# 05_-_NIXIE.net
KiCad netlist of a schematic drawn in Altium Designer
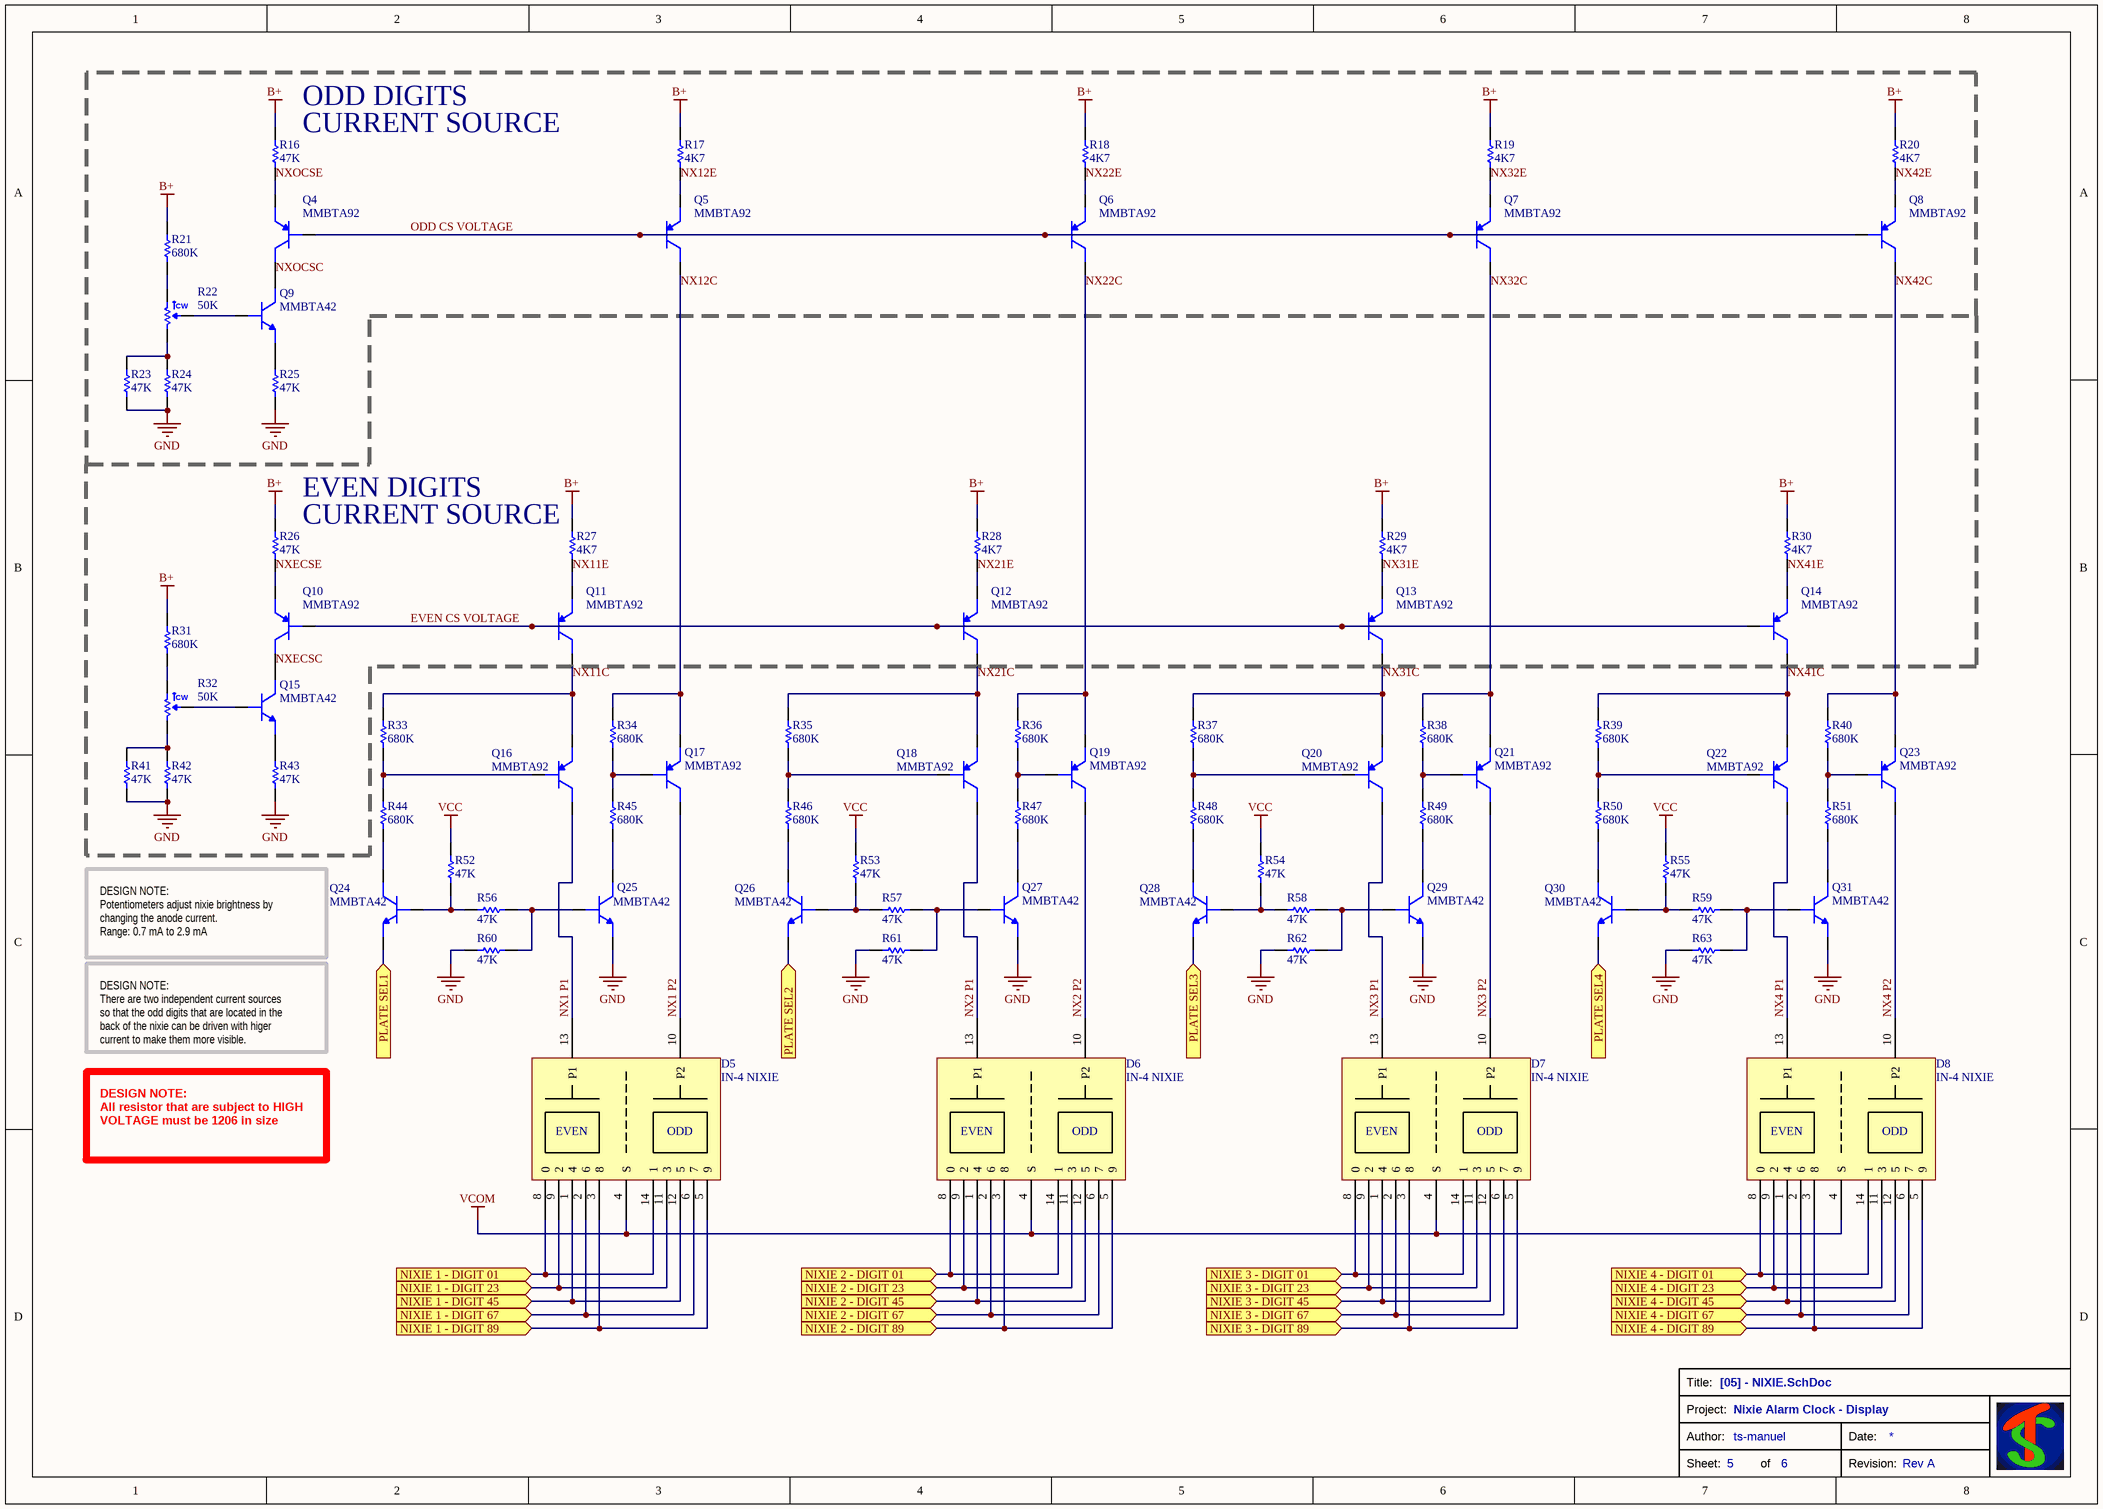
[diagram p0: [05] - NIXIE.SchDoc]

(export (version "E")
  (design (tool "Eeschema 10.0.6"))
  (components
    (comp (ref "D5")
      (value "IN-4 NIXIE")
      (footprint "IN4 NIXIE")
      (libsource (lib "mt_local_library") (part "IN-4 NIXIE"))
    )
    (comp (ref "D6")
      (value "IN-4 NIXIE")
      (footprint "IN4 NIXIE")
      (libsource (lib "mt_local_library") (part "IN-4 NIXIE"))
    )
    (comp (ref "D7")
      (value "IN-4 NIXIE")
      (footprint "IN4 NIXIE")
      (libsource (lib "mt_local_library") (part "IN-4 NIXIE"))
    )
    (comp (ref "D8")
      (value "IN-4 NIXIE")
      (footprint "IN4 NIXIE")
      (libsource (lib "mt_local_library") (part "IN-4 NIXIE"))
    )
    (comp (ref "Q4")
      (value "MMBTA92")
      (footprint "SOT95P240X110-3N")
      (description "300V PNP SMALL SIGNAL TRANSISTOR IN SOT23")
      (libsource (lib "mt_local_library") (part "PNP-MMBTA92"))
    )
    (comp (ref "Q5")
      (value "MMBTA92")
      (footprint "SOT95P240X110-3N")
      (description "300V PNP SMALL SIGNAL TRANSISTOR IN SOT23")
      (libsource (lib "mt_local_library") (part "PNP-MMBTA92"))
    )
    (comp (ref "Q6")
      (value "MMBTA92")
      (footprint "SOT95P240X110-3N")
      (description "300V PNP SMALL SIGNAL TRANSISTOR IN SOT23")
      (libsource (lib "mt_local_library") (part "PNP-MMBTA92"))
    )
    (comp (ref "Q7")
      (value "MMBTA92")
      (footprint "SOT95P240X110-3N")
      (description "300V PNP SMALL SIGNAL TRANSISTOR IN SOT23")
      (libsource (lib "mt_local_library") (part "PNP-MMBTA92"))
    )
    (comp (ref "Q8")
      (value "MMBTA92")
      (footprint "SOT95P240X110-3N")
      (description "300V PNP SMALL SIGNAL TRANSISTOR IN SOT23")
      (libsource (lib "mt_local_library") (part "PNP-MMBTA92"))
    )
    (comp (ref "Q9")
      (value "MMBTA42")
      (footprint "SOT95P240X110-3N")
      (description "300V NPN SMALL SIGNAL TRANSISTOR IN SOT23")
      (libsource (lib "mt_local_library") (part "NPN-MMBTA42"))
    )
    (comp (ref "Q10")
      (value "MMBTA92")
      (footprint "SOT95P240X110-3N")
      (description "300V PNP SMALL SIGNAL TRANSISTOR IN SOT23")
      (libsource (lib "mt_local_library") (part "PNP-MMBTA92"))
    )
    (comp (ref "Q11")
      (value "MMBTA92")
      (footprint "SOT95P240X110-3N")
      (description "300V PNP SMALL SIGNAL TRANSISTOR IN SOT23")
      (libsource (lib "mt_local_library") (part "PNP-MMBTA92"))
    )
    (comp (ref "Q12")
      (value "MMBTA92")
      (footprint "SOT95P240X110-3N")
      (description "300V PNP SMALL SIGNAL TRANSISTOR IN SOT23")
      (libsource (lib "mt_local_library") (part "PNP-MMBTA92"))
    )
    (comp (ref "Q13")
      (value "MMBTA92")
      (footprint "SOT95P240X110-3N")
      (description "300V PNP SMALL SIGNAL TRANSISTOR IN SOT23")
      (libsource (lib "mt_local_library") (part "PNP-MMBTA92"))
    )
    (comp (ref "Q14")
      (value "MMBTA92")
      (footprint "SOT95P240X110-3N")
      (description "300V PNP SMALL SIGNAL TRANSISTOR IN SOT23")
      (libsource (lib "mt_local_library") (part "PNP-MMBTA92"))
    )
    (comp (ref "Q15")
      (value "MMBTA42")
      (footprint "SOT95P240X110-3N")
      (description "300V NPN SMALL SIGNAL TRANSISTOR IN SOT23")
      (libsource (lib "mt_local_library") (part "NPN-MMBTA42"))
    )
    (comp (ref "Q16")
      (value "MMBTA92")
      (footprint "SOT95P240X110-3N")
      (description "300V PNP SMALL SIGNAL TRANSISTOR IN SOT23")
      (libsource (lib "mt_local_library") (part "PNP-MMBTA92"))
    )
    (comp (ref "Q17")
      (value "MMBTA92")
      (footprint "SOT95P240X110-3N")
      (description "300V PNP SMALL SIGNAL TRANSISTOR IN SOT23")
      (libsource (lib "mt_local_library") (part "PNP-MMBTA92"))
    )
    (comp (ref "Q18")
      (value "MMBTA92")
      (footprint "SOT95P240X110-3N")
      (description "300V PNP SMALL SIGNAL TRANSISTOR IN SOT23")
      (libsource (lib "mt_local_library") (part "PNP-MMBTA92"))
    )
    (comp (ref "Q19")
      (value "MMBTA92")
      (footprint "SOT95P240X110-3N")
      (description "300V PNP SMALL SIGNAL TRANSISTOR IN SOT23")
      (libsource (lib "mt_local_library") (part "PNP-MMBTA92"))
    )
    (comp (ref "Q20")
      (value "MMBTA92")
      (footprint "SOT95P240X110-3N")
      (description "300V PNP SMALL SIGNAL TRANSISTOR IN SOT23")
      (libsource (lib "mt_local_library") (part "PNP-MMBTA92"))
    )
    (comp (ref "Q21")
      (value "MMBTA92")
      (footprint "SOT95P240X110-3N")
      (description "300V PNP SMALL SIGNAL TRANSISTOR IN SOT23")
      (libsource (lib "mt_local_library") (part "PNP-MMBTA92"))
    )
    (comp (ref "Q22")
      (value "MMBTA92")
      (footprint "SOT95P240X110-3N")
      (description "300V PNP SMALL SIGNAL TRANSISTOR IN SOT23")
      (libsource (lib "mt_local_library") (part "PNP-MMBTA92"))
    )
    (comp (ref "Q23")
      (value "MMBTA92")
      (footprint "SOT95P240X110-3N")
      (description "300V PNP SMALL SIGNAL TRANSISTOR IN SOT23")
      (libsource (lib "mt_local_library") (part "PNP-MMBTA92"))
    )
    (comp (ref "Q24")
      (value "MMBTA42")
      (footprint "SOT95P240X110-3N")
      (description "300V NPN SMALL SIGNAL TRANSISTOR IN SOT23")
      (libsource (lib "mt_local_library") (part "NPN-MMBTA42"))
    )
    (comp (ref "Q25")
      (value "MMBTA42")
      (footprint "SOT95P240X110-3N")
      (description "300V NPN SMALL SIGNAL TRANSISTOR IN SOT23")
      (libsource (lib "mt_local_library") (part "NPN-MMBTA42"))
    )
    (comp (ref "Q26")
      (value "MMBTA42")
      (footprint "SOT95P240X110-3N")
      (description "300V NPN SMALL SIGNAL TRANSISTOR IN SOT23")
      (libsource (lib "mt_local_library") (part "NPN-MMBTA42"))
    )
    (comp (ref "Q27")
      (value "MMBTA42")
      (footprint "SOT95P240X110-3N")
      (description "300V NPN SMALL SIGNAL TRANSISTOR IN SOT23")
      (libsource (lib "mt_local_library") (part "NPN-MMBTA42"))
    )
    (comp (ref "Q28")
      (value "MMBTA42")
      (footprint "SOT95P240X110-3N")
      (description "300V NPN SMALL SIGNAL TRANSISTOR IN SOT23")
      (libsource (lib "mt_local_library") (part "NPN-MMBTA42"))
    )
    (comp (ref "Q29")
      (value "MMBTA42")
      (footprint "SOT95P240X110-3N")
      (description "300V NPN SMALL SIGNAL TRANSISTOR IN SOT23")
      (libsource (lib "mt_local_library") (part "NPN-MMBTA42"))
    )
    (comp (ref "Q30")
      (value "MMBTA42")
      (footprint "SOT95P240X110-3N")
      (description "300V NPN SMALL SIGNAL TRANSISTOR IN SOT23")
      (libsource (lib "mt_local_library") (part "NPN-MMBTA42"))
    )
    (comp (ref "Q31")
      (value "MMBTA42")
      (footprint "SOT95P240X110-3N")
      (description "300V NPN SMALL SIGNAL TRANSISTOR IN SOT23")
      (libsource (lib "mt_local_library") (part "NPN-MMBTA42"))
    )
    (comp (ref "R16")
      (value "47K")
      (footprint "RES-0805")
      (description "Thin Film Resistors 1/8W 47K ohm 1% 50ppm")
      (fields (field (name "MANUFACTURER") "Yageo") (field (name "TOLERANCE") "1%"))
      (libsource (lib "mt_local_library") (part "RES-0805-47K-RT0805FRE0747KL"))
    )
    (comp (ref "R17")
      (value "4K7")
      (footprint "RES-0805")
      (description "Thin Film Resistors 4.7K ohm 1% 50 ppm")
      (fields (field (name "MANUFACTURER") "Yageo") (field (name "TOLERANCE") "1%"))
      (libsource (lib "mt_local_library") (part "RES-0805-4K7-RT0805FRE134K7L"))
    )
    (comp (ref "R18")
      (value "4K7")
      (footprint "RES-0805")
      (description "Thin Film Resistors 4.7K ohm 1% 50 ppm")
      (fields (field (name "MANUFACTURER") "Yageo") (field (name "TOLERANCE") "1%"))
      (libsource (lib "mt_local_library") (part "RES-0805-4K7-RT0805FRE134K7L"))
    )
    (comp (ref "R19")
      (value "4K7")
      (footprint "RES-0805")
      (description "Thin Film Resistors 4.7K ohm 1% 50 ppm")
      (fields (field (name "MANUFACTURER") "Yageo") (field (name "TOLERANCE") "1%"))
      (libsource (lib "mt_local_library") (part "RES-0805-4K7-RT0805FRE134K7L"))
    )
    (comp (ref "R20")
      (value "4K7")
      (footprint "RES-0805")
      (description "Thin Film Resistors 4.7K ohm 1% 50 ppm")
      (fields (field (name "MANUFACTURER") "Yageo") (field (name "TOLERANCE") "1%"))
      (libsource (lib "mt_local_library") (part "RES-0805-4K7-RT0805FRE134K7L"))
    )
    (comp (ref "R21")
      (value "680K")
      (footprint "RES-1206")
      (description "Thin Film Resistors 680K OHM 1% 50PPM 1/4W")
      (fields (field (name "MANUFACTURER") "Yageo") (field (name "TOLERANCE") "1%"))
      (libsource (lib "mt_local_library") (part "RES-1206-680K-RT1206FRE07680KL"))
    )
    (comp (ref "R22")
      (value "50K")
      (footprint "TC33X2503E")
      (description "Resistenze trimmer - SMD 3MM 50KOHMS 25% 0.1WATT OPEN FRM")
      (fields (field (name "MANUFACTURER") "Yageo") (field (name "TOLERANCE") "1%"))
      (libsource (lib "mt_local_library") (part "POT-50K-TC33X-2-503E"))
    )
    (comp (ref "R23")
      (value "47K")
      (footprint "RES-0805")
      (description "Thin Film Resistors 1/8W 47K ohm 1% 50ppm")
      (fields (field (name "MANUFACTURER") "Yageo") (field (name "TOLERANCE") "1%"))
      (libsource (lib "mt_local_library") (part "RES-0805-47K-RT0805FRE0747KL"))
    )
    (comp (ref "R24")
      (value "47K")
      (footprint "RES-0805")
      (description "Thin Film Resistors 1/8W 47K ohm 1% 50ppm")
      (fields (field (name "MANUFACTURER") "Yageo") (field (name "TOLERANCE") "1%"))
      (libsource (lib "mt_local_library") (part "RES-0805-47K-RT0805FRE0747KL"))
    )
    (comp (ref "R25")
      (value "47K")
      (footprint "RES-0805")
      (description "Thin Film Resistors 1/8W 47K ohm 1% 50ppm")
      (fields (field (name "MANUFACTURER") "Yageo") (field (name "TOLERANCE") "1%"))
      (libsource (lib "mt_local_library") (part "RES-0805-47K-RT0805FRE0747KL"))
    )
    (comp (ref "R26")
      (value "47K")
      (footprint "RES-0805")
      (description "Thin Film Resistors 1/8W 47K ohm 1% 50ppm")
      (fields (field (name "MANUFACTURER") "Yageo") (field (name "TOLERANCE") "1%"))
      (libsource (lib "mt_local_library") (part "RES-0805-47K-RT0805FRE0747KL"))
    )
    (comp (ref "R27")
      (value "4K7")
      (footprint "RES-0805")
      (description "Thin Film Resistors 4.7K ohm 1% 50 ppm")
      (fields (field (name "MANUFACTURER") "Yageo") (field (name "TOLERANCE") "1%"))
      (libsource (lib "mt_local_library") (part "RES-0805-4K7-RT0805FRE134K7L"))
    )
    (comp (ref "R28")
      (value "4K7")
      (footprint "RES-0805")
      (description "Thin Film Resistors 4.7K ohm 1% 50 ppm")
      (fields (field (name "MANUFACTURER") "Yageo") (field (name "TOLERANCE") "1%"))
      (libsource (lib "mt_local_library") (part "RES-0805-4K7-RT0805FRE134K7L"))
    )
    (comp (ref "R29")
      (value "4K7")
      (footprint "RES-0805")
      (description "Thin Film Resistors 4.7K ohm 1% 50 ppm")
      (fields (field (name "MANUFACTURER") "Yageo") (field (name "TOLERANCE") "1%"))
      (libsource (lib "mt_local_library") (part "RES-0805-4K7-RT0805FRE134K7L"))
    )
    (comp (ref "R30")
      (value "4K7")
      (footprint "RES-0805")
      (description "Thin Film Resistors 4.7K ohm 1% 50 ppm")
      (fields (field (name "MANUFACTURER") "Yageo") (field (name "TOLERANCE") "1%"))
      (libsource (lib "mt_local_library") (part "RES-0805-4K7-RT0805FRE134K7L"))
    )
    (comp (ref "R31")
      (value "680K")
      (footprint "RES-1206")
      (description "Thin Film Resistors 680K OHM 1% 50PPM 1/4W")
      (fields (field (name "MANUFACTURER") "Yageo") (field (name "TOLERANCE") "1%"))
      (libsource (lib "mt_local_library") (part "RES-1206-680K-RT1206FRE07680KL"))
    )
    (comp (ref "R32")
      (value "50K")
      (footprint "TC33X2503E")
      (description "Resistenze trimmer - SMD 3MM 50KOHMS 25% 0.1WATT OPEN FRM")
      (fields (field (name "MANUFACTURER") "Yageo") (field (name "TOLERANCE") "1%"))
      (libsource (lib "mt_local_library") (part "POT-50K-TC33X-2-503E"))
    )
    (comp (ref "R33")
      (value "680K")
      (footprint "RES-1206")
      (description "Thin Film Resistors 680K OHM 1% 50PPM 1/4W")
      (fields (field (name "MANUFACTURER") "Yageo") (field (name "TOLERANCE") "1%"))
      (libsource (lib "mt_local_library") (part "RES-1206-680K-RT1206FRE07680KL"))
    )
    (comp (ref "R34")
      (value "680K")
      (footprint "RES-1206")
      (description "Thin Film Resistors 680K OHM 1% 50PPM 1/4W")
      (fields (field (name "MANUFACTURER") "Yageo") (field (name "TOLERANCE") "1%"))
      (libsource (lib "mt_local_library") (part "RES-1206-680K-RT1206FRE07680KL"))
    )
    (comp (ref "R35")
      (value "680K")
      (footprint "RES-1206")
      (description "Thin Film Resistors 680K OHM 1% 50PPM 1/4W")
      (fields (field (name "MANUFACTURER") "Yageo") (field (name "TOLERANCE") "1%"))
      (libsource (lib "mt_local_library") (part "RES-1206-680K-RT1206FRE07680KL"))
    )
    (comp (ref "R36")
      (value "680K")
      (footprint "RES-1206")
      (description "Thin Film Resistors 680K OHM 1% 50PPM 1/4W")
      (fields (field (name "MANUFACTURER") "Yageo") (field (name "TOLERANCE") "1%"))
      (libsource (lib "mt_local_library") (part "RES-1206-680K-RT1206FRE07680KL"))
    )
    (comp (ref "R37")
      (value "680K")
      (footprint "RES-1206")
      (description "Thin Film Resistors 680K OHM 1% 50PPM 1/4W")
      (fields (field (name "MANUFACTURER") "Yageo") (field (name "TOLERANCE") "1%"))
      (libsource (lib "mt_local_library") (part "RES-1206-680K-RT1206FRE07680KL"))
    )
    (comp (ref "R38")
      (value "680K")
      (footprint "RES-1206")
      (description "Thin Film Resistors 680K OHM 1% 50PPM 1/4W")
      (fields (field (name "MANUFACTURER") "Yageo") (field (name "TOLERANCE") "1%"))
      (libsource (lib "mt_local_library") (part "RES-1206-680K-RT1206FRE07680KL"))
    )
    (comp (ref "R39")
      (value "680K")
      (footprint "RES-1206")
      (description "Thin Film Resistors 680K OHM 1% 50PPM 1/4W")
      (fields (field (name "MANUFACTURER") "Yageo") (field (name "TOLERANCE") "1%"))
      (libsource (lib "mt_local_library") (part "RES-1206-680K-RT1206FRE07680KL"))
    )
    (comp (ref "R40")
      (value "680K")
      (footprint "RES-1206")
      (description "Thin Film Resistors 680K OHM 1% 50PPM 1/4W")
      (fields (field (name "MANUFACTURER") "Yageo") (field (name "TOLERANCE") "1%"))
      (libsource (lib "mt_local_library") (part "RES-1206-680K-RT1206FRE07680KL"))
    )
    (comp (ref "R41")
      (value "47K")
      (footprint "RES-0805")
      (description "Thin Film Resistors 1/8W 47K ohm 1% 50ppm")
      (fields (field (name "MANUFACTURER") "Yageo") (field (name "TOLERANCE") "1%"))
      (libsource (lib "mt_local_library") (part "RES-0805-47K-RT0805FRE0747KL"))
    )
    (comp (ref "R42")
      (value "47K")
      (footprint "RES-0805")
      (description "Thin Film Resistors 1/8W 47K ohm 1% 50ppm")
      (fields (field (name "MANUFACTURER") "Yageo") (field (name "TOLERANCE") "1%"))
      (libsource (lib "mt_local_library") (part "RES-0805-47K-RT0805FRE0747KL"))
    )
    (comp (ref "R43")
      (value "47K")
      (footprint "RES-0805")
      (description "Thin Film Resistors 1/8W 47K ohm 1% 50ppm")
      (fields (field (name "MANUFACTURER") "Yageo") (field (name "TOLERANCE") "1%"))
      (libsource (lib "mt_local_library") (part "RES-0805-47K-RT0805FRE0747KL"))
    )
    (comp (ref "R44")
      (value "680K")
      (footprint "RES-1206")
      (description "Thin Film Resistors 680K OHM 1% 50PPM 1/4W")
      (fields (field (name "MANUFACTURER") "Yageo") (field (name "TOLERANCE") "1%"))
      (libsource (lib "mt_local_library") (part "RES-1206-680K-RT1206FRE07680KL"))
    )
    (comp (ref "R45")
      (value "680K")
      (footprint "RES-1206")
      (description "Thin Film Resistors 680K OHM 1% 50PPM 1/4W")
      (fields (field (name "MANUFACTURER") "Yageo") (field (name "TOLERANCE") "1%"))
      (libsource (lib "mt_local_library") (part "RES-1206-680K-RT1206FRE07680KL"))
    )
    (comp (ref "R46")
      (value "680K")
      (footprint "RES-1206")
      (description "Thin Film Resistors 680K OHM 1% 50PPM 1/4W")
      (fields (field (name "MANUFACTURER") "Yageo") (field (name "TOLERANCE") "1%"))
      (libsource (lib "mt_local_library") (part "RES-1206-680K-RT1206FRE07680KL"))
    )
    (comp (ref "R47")
      (value "680K")
      (footprint "RES-1206")
      (description "Thin Film Resistors 680K OHM 1% 50PPM 1/4W")
      (fields (field (name "MANUFACTURER") "Yageo") (field (name "TOLERANCE") "1%"))
      (libsource (lib "mt_local_library") (part "RES-1206-680K-RT1206FRE07680KL"))
    )
    (comp (ref "R48")
      (value "680K")
      (footprint "RES-1206")
      (description "Thin Film Resistors 680K OHM 1% 50PPM 1/4W")
      (fields (field (name "MANUFACTURER") "Yageo") (field (name "TOLERANCE") "1%"))
      (libsource (lib "mt_local_library") (part "RES-1206-680K-RT1206FRE07680KL"))
    )
    (comp (ref "R49")
      (value "680K")
      (footprint "RES-1206")
      (description "Thin Film Resistors 680K OHM 1% 50PPM 1/4W")
      (fields (field (name "MANUFACTURER") "Yageo") (field (name "TOLERANCE") "1%"))
      (libsource (lib "mt_local_library") (part "RES-1206-680K-RT1206FRE07680KL"))
    )
    (comp (ref "R50")
      (value "680K")
      (footprint "RES-1206")
      (description "Thin Film Resistors 680K OHM 1% 50PPM 1/4W")
      (fields (field (name "MANUFACTURER") "Yageo") (field (name "TOLERANCE") "1%"))
      (libsource (lib "mt_local_library") (part "RES-1206-680K-RT1206FRE07680KL"))
    )
    (comp (ref "R51")
      (value "680K")
      (footprint "RES-1206")
      (description "Thin Film Resistors 680K OHM 1% 50PPM 1/4W")
      (fields (field (name "MANUFACTURER") "Yageo") (field (name "TOLERANCE") "1%"))
      (libsource (lib "mt_local_library") (part "RES-1206-680K-RT1206FRE07680KL"))
    )
    (comp (ref "R52")
      (value "47K")
      (footprint "RES-0805")
      (description "Thin Film Resistors 1/8W 47K ohm 1% 50ppm")
      (fields (field (name "MANUFACTURER") "Yageo") (field (name "TOLERANCE") "1%"))
      (libsource (lib "mt_local_library") (part "RES-0805-47K-RT0805FRE0747KL"))
    )
    (comp (ref "R53")
      (value "47K")
      (footprint "RES-0805")
      (description "Thin Film Resistors 1/8W 47K ohm 1% 50ppm")
      (fields (field (name "MANUFACTURER") "Yageo") (field (name "TOLERANCE") "1%"))
      (libsource (lib "mt_local_library") (part "RES-0805-47K-RT0805FRE0747KL"))
    )
    (comp (ref "R54")
      (value "47K")
      (footprint "RES-0805")
      (description "Thin Film Resistors 1/8W 47K ohm 1% 50ppm")
      (fields (field (name "MANUFACTURER") "Yageo") (field (name "TOLERANCE") "1%"))
      (libsource (lib "mt_local_library") (part "RES-0805-47K-RT0805FRE0747KL"))
    )
    (comp (ref "R55")
      (value "47K")
      (footprint "RES-0805")
      (description "Thin Film Resistors 1/8W 47K ohm 1% 50ppm")
      (fields (field (name "MANUFACTURER") "Yageo") (field (name "TOLERANCE") "1%"))
      (libsource (lib "mt_local_library") (part "RES-0805-47K-RT0805FRE0747KL"))
    )
    (comp (ref "R56")
      (value "47K")
      (footprint "RES-0805")
      (description "Thin Film Resistors 1/8W 47K ohm 1% 50ppm")
      (fields (field (name "MANUFACTURER") "Yageo") (field (name "TOLERANCE") "1%"))
      (libsource (lib "mt_local_library") (part "RES-0805-47K-RT0805FRE0747KL"))
    )
    (comp (ref "R57")
      (value "47K")
      (footprint "RES-0805")
      (description "Thin Film Resistors 1/8W 47K ohm 1% 50ppm")
      (fields (field (name "MANUFACTURER") "Yageo") (field (name "TOLERANCE") "1%"))
      (libsource (lib "mt_local_library") (part "RES-0805-47K-RT0805FRE0747KL"))
    )
    (comp (ref "R58")
      (value "47K")
      (footprint "RES-0805")
      (description "Thin Film Resistors 1/8W 47K ohm 1% 50ppm")
      (fields (field (name "MANUFACTURER") "Yageo") (field (name "TOLERANCE") "1%"))
      (libsource (lib "mt_local_library") (part "RES-0805-47K-RT0805FRE0747KL"))
    )
    (comp (ref "R59")
      (value "47K")
      (footprint "RES-0805")
      (description "Thin Film Resistors 1/8W 47K ohm 1% 50ppm")
      (fields (field (name "MANUFACTURER") "Yageo") (field (name "TOLERANCE") "1%"))
      (libsource (lib "mt_local_library") (part "RES-0805-47K-RT0805FRE0747KL"))
    )
    (comp (ref "R60")
      (value "47K")
      (footprint "RES-0805")
      (description "Thin Film Resistors 1/8W 47K ohm 1% 50ppm")
      (fields (field (name "MANUFACTURER") "Yageo") (field (name "TOLERANCE") "1%"))
      (libsource (lib "mt_local_library") (part "RES-0805-47K-RT0805FRE0747KL"))
    )
    (comp (ref "R61")
      (value "47K")
      (footprint "RES-0805")
      (description "Thin Film Resistors 1/8W 47K ohm 1% 50ppm")
      (fields (field (name "MANUFACTURER") "Yageo") (field (name "TOLERANCE") "1%"))
      (libsource (lib "mt_local_library") (part "RES-0805-47K-RT0805FRE0747KL"))
    )
    (comp (ref "R62")
      (value "47K")
      (footprint "RES-0805")
      (description "Thin Film Resistors 1/8W 47K ohm 1% 50ppm")
      (fields (field (name "MANUFACTURER") "Yageo") (field (name "TOLERANCE") "1%"))
      (libsource (lib "mt_local_library") (part "RES-0805-47K-RT0805FRE0747KL"))
    )
    (comp (ref "R63")
      (value "47K")
      (footprint "RES-0805")
      (description "Thin Film Resistors 1/8W 47K ohm 1% 50ppm")
      (fields (field (name "MANUFACTURER") "Yageo") (field (name "TOLERANCE") "1%"))
      (libsource (lib "mt_local_library") (part "RES-0805-47K-RT0805FRE0747KL"))
    )
  )
  (nets
    (net (code "1") (name "/EVEN CS VOLTAGE") (class "Default")
      (node (ref "Q10") (pin "1") (pinfunction "B_1") (pintype "passive"))
      (node (ref "Q11") (pin "1") (pinfunction "B_1") (pintype "passive"))
      (node (ref "Q12") (pin "1") (pinfunction "B_1") (pintype "passive"))
      (node (ref "Q13") (pin "1") (pinfunction "B_1") (pintype "passive"))
      (node (ref "Q14") (pin "1") (pinfunction "B_1") (pintype "passive"))
    )
    (net (code "2") (name "/NIXIE 1 - DIGIT 01") (class "Default")
      (node (ref "D5") (pin "14") (pinfunction "1_14") (pintype "passive"))
      (node (ref "D5") (pin "8") (pinfunction "0_8") (pintype "passive"))
    )
    (net (code "3") (name "/NIXIE 1 - DIGIT 23") (class "Default")
      (node (ref "D5") (pin "11") (pinfunction "3_11") (pintype "passive"))
      (node (ref "D5") (pin "9") (pinfunction "2_9") (pintype "passive"))
    )
    (net (code "4") (name "/NIXIE 1 - DIGIT 45") (class "Default")
      (node (ref "D5") (pin "1") (pinfunction "4_1") (pintype "passive"))
      (node (ref "D5") (pin "12") (pinfunction "5_12") (pintype "passive"))
    )
    (net (code "5") (name "/NIXIE 1 - DIGIT 67") (class "Default")
      (node (ref "D5") (pin "2") (pinfunction "6_2") (pintype "passive"))
      (node (ref "D5") (pin "6") (pinfunction "7_6") (pintype "passive"))
    )
    (net (code "6") (name "/NIXIE 1 - DIGIT 89") (class "Default")
      (node (ref "D5") (pin "3") (pinfunction "8_3") (pintype "passive"))
      (node (ref "D5") (pin "5") (pinfunction "9_5") (pintype "passive"))
    )
    (net (code "7") (name "/NIXIE 2 - DIGIT 01") (class "Default")
      (node (ref "D6") (pin "14") (pinfunction "1_14") (pintype "passive"))
      (node (ref "D6") (pin "8") (pinfunction "0_8") (pintype "passive"))
    )
    (net (code "8") (name "/NIXIE 2 - DIGIT 23") (class "Default")
      (node (ref "D6") (pin "11") (pinfunction "3_11") (pintype "passive"))
      (node (ref "D6") (pin "9") (pinfunction "2_9") (pintype "passive"))
    )
    (net (code "9") (name "/NIXIE 2 - DIGIT 45") (class "Default")
      (node (ref "D6") (pin "1") (pinfunction "4_1") (pintype "passive"))
      (node (ref "D6") (pin "12") (pinfunction "5_12") (pintype "passive"))
    )
    (net (code "10") (name "/NIXIE 2 - DIGIT 67") (class "Default")
      (node (ref "D6") (pin "2") (pinfunction "6_2") (pintype "passive"))
      (node (ref "D6") (pin "6") (pinfunction "7_6") (pintype "passive"))
    )
    (net (code "11") (name "/NIXIE 2 - DIGIT 89") (class "Default")
      (node (ref "D6") (pin "3") (pinfunction "8_3") (pintype "passive"))
      (node (ref "D6") (pin "5") (pinfunction "9_5") (pintype "passive"))
    )
    (net (code "12") (name "/NIXIE 3 - DIGIT 01") (class "Default")
      (node (ref "D7") (pin "14") (pinfunction "1_14") (pintype "passive"))
      (node (ref "D7") (pin "8") (pinfunction "0_8") (pintype "passive"))
    )
    (net (code "13") (name "/NIXIE 3 - DIGIT 23") (class "Default")
      (node (ref "D7") (pin "11") (pinfunction "3_11") (pintype "passive"))
      (node (ref "D7") (pin "9") (pinfunction "2_9") (pintype "passive"))
    )
    (net (code "14") (name "/NIXIE 3 - DIGIT 45") (class "Default")
      (node (ref "D7") (pin "1") (pinfunction "4_1") (pintype "passive"))
      (node (ref "D7") (pin "12") (pinfunction "5_12") (pintype "passive"))
    )
    (net (code "15") (name "/NIXIE 3 - DIGIT 67") (class "Default")
      (node (ref "D7") (pin "2") (pinfunction "6_2") (pintype "passive"))
      (node (ref "D7") (pin "6") (pinfunction "7_6") (pintype "passive"))
    )
    (net (code "16") (name "/NIXIE 3 - DIGIT 89") (class "Default")
      (node (ref "D7") (pin "3") (pinfunction "8_3") (pintype "passive"))
      (node (ref "D7") (pin "5") (pinfunction "9_5") (pintype "passive"))
    )
    (net (code "17") (name "/NIXIE 4 - DIGIT 01") (class "Default")
      (node (ref "D8") (pin "14") (pinfunction "1_14") (pintype "passive"))
      (node (ref "D8") (pin "8") (pinfunction "0_8") (pintype "passive"))
    )
    (net (code "18") (name "/NIXIE 4 - DIGIT 23") (class "Default")
      (node (ref "D8") (pin "11") (pinfunction "3_11") (pintype "passive"))
      (node (ref "D8") (pin "9") (pinfunction "2_9") (pintype "passive"))
    )
    (net (code "19") (name "/NIXIE 4 - DIGIT 45") (class "Default")
      (node (ref "D8") (pin "1") (pinfunction "4_1") (pintype "passive"))
      (node (ref "D8") (pin "12") (pinfunction "5_12") (pintype "passive"))
    )
    (net (code "20") (name "/NIXIE 4 - DIGIT 67") (class "Default")
      (node (ref "D8") (pin "2") (pinfunction "6_2") (pintype "passive"))
      (node (ref "D8") (pin "6") (pinfunction "7_6") (pintype "passive"))
    )
    (net (code "21") (name "/NIXIE 4 - DIGIT 89") (class "Default")
      (node (ref "D8") (pin "3") (pinfunction "8_3") (pintype "passive"))
      (node (ref "D8") (pin "5") (pinfunction "9_5") (pintype "passive"))
    )
    (net (code "22") (name "/NX1 P1") (class "Default")
      (node (ref "D5") (pin "13") (pinfunction "P1_13") (pintype "passive"))
      (node (ref "Q16") (pin "3") (pinfunction "C_3") (pintype "passive"))
    )
    (net (code "23") (name "/NX1 P2") (class "Default")
      (node (ref "D5") (pin "10") (pinfunction "P2_10") (pintype "passive"))
      (node (ref "Q17") (pin "3") (pinfunction "C_3") (pintype "passive"))
    )
    (net (code "24") (name "/NX2 P1") (class "Default")
      (node (ref "D6") (pin "13") (pinfunction "P1_13") (pintype "passive"))
      (node (ref "Q18") (pin "3") (pinfunction "C_3") (pintype "passive"))
    )
    (net (code "25") (name "/NX2 P2") (class "Default")
      (node (ref "D6") (pin "10") (pinfunction "P2_10") (pintype "passive"))
      (node (ref "Q19") (pin "3") (pinfunction "C_3") (pintype "passive"))
    )
    (net (code "26") (name "/NX3 P1") (class "Default")
      (node (ref "D7") (pin "13") (pinfunction "P1_13") (pintype "passive"))
      (node (ref "Q20") (pin "3") (pinfunction "C_3") (pintype "passive"))
    )
    (net (code "27") (name "/NX3 P2") (class "Default")
      (node (ref "D7") (pin "10") (pinfunction "P2_10") (pintype "passive"))
      (node (ref "Q21") (pin "3") (pinfunction "C_3") (pintype "passive"))
    )
    (net (code "28") (name "/NX4 P1") (class "Default")
      (node (ref "D8") (pin "13") (pinfunction "P1_13") (pintype "passive"))
      (node (ref "Q22") (pin "3") (pinfunction "C_3") (pintype "passive"))
    )
    (net (code "29") (name "/NX4 P2") (class "Default")
      (node (ref "D8") (pin "10") (pinfunction "P2_10") (pintype "passive"))
      (node (ref "Q23") (pin "3") (pinfunction "C_3") (pintype "passive"))
    )
    (net (code "30") (name "/NX11C") (class "Default")
      (node (ref "Q11") (pin "3") (pinfunction "C_3") (pintype "passive"))
      (node (ref "Q16") (pin "2") (pinfunction "E_2") (pintype "passive"))
      (node (ref "R33") (pin "2") (pinfunction "2_2") (pintype "passive"))
    )
    (net (code "31") (name "/NX11E") (class "Default")
      (node (ref "Q11") (pin "2") (pinfunction "E_2") (pintype "passive"))
      (node (ref "R27") (pin "1") (pinfunction "1_1") (pintype "passive"))
    )
    (net (code "32") (name "/NX12C") (class "Default")
      (node (ref "Q17") (pin "2") (pinfunction "E_2") (pintype "passive"))
      (node (ref "Q5") (pin "3") (pinfunction "C_3") (pintype "passive"))
      (node (ref "R34") (pin "2") (pinfunction "2_2") (pintype "passive"))
    )
    (net (code "33") (name "/NX12E") (class "Default")
      (node (ref "Q5") (pin "2") (pinfunction "E_2") (pintype "passive"))
      (node (ref "R17") (pin "1") (pinfunction "1_1") (pintype "passive"))
    )
    (net (code "34") (name "/NX21C") (class "Default")
      (node (ref "Q12") (pin "3") (pinfunction "C_3") (pintype "passive"))
      (node (ref "Q18") (pin "2") (pinfunction "E_2") (pintype "passive"))
      (node (ref "R35") (pin "2") (pinfunction "2_2") (pintype "passive"))
    )
    (net (code "35") (name "/NX21E") (class "Default")
      (node (ref "Q12") (pin "2") (pinfunction "E_2") (pintype "passive"))
      (node (ref "R28") (pin "1") (pinfunction "1_1") (pintype "passive"))
    )
    (net (code "36") (name "/NX22C") (class "Default")
      (node (ref "Q19") (pin "2") (pinfunction "E_2") (pintype "passive"))
      (node (ref "Q6") (pin "3") (pinfunction "C_3") (pintype "passive"))
      (node (ref "R36") (pin "2") (pinfunction "2_2") (pintype "passive"))
    )
    (net (code "37") (name "/NX22E") (class "Default")
      (node (ref "Q6") (pin "2") (pinfunction "E_2") (pintype "passive"))
      (node (ref "R18") (pin "1") (pinfunction "1_1") (pintype "passive"))
    )
    (net (code "38") (name "/NX31C") (class "Default")
      (node (ref "Q13") (pin "3") (pinfunction "C_3") (pintype "passive"))
      (node (ref "Q20") (pin "2") (pinfunction "E_2") (pintype "passive"))
      (node (ref "R37") (pin "2") (pinfunction "2_2") (pintype "passive"))
    )
    (net (code "39") (name "/NX31E") (class "Default")
      (node (ref "Q13") (pin "2") (pinfunction "E_2") (pintype "passive"))
      (node (ref "R29") (pin "1") (pinfunction "1_1") (pintype "passive"))
    )
    (net (code "40") (name "/NX32C") (class "Default")
      (node (ref "Q21") (pin "2") (pinfunction "E_2") (pintype "passive"))
      (node (ref "Q7") (pin "3") (pinfunction "C_3") (pintype "passive"))
      (node (ref "R38") (pin "2") (pinfunction "2_2") (pintype "passive"))
    )
    (net (code "41") (name "/NX32E") (class "Default")
      (node (ref "Q7") (pin "2") (pinfunction "E_2") (pintype "passive"))
      (node (ref "R19") (pin "1") (pinfunction "1_1") (pintype "passive"))
    )
    (net (code "42") (name "/NX41C") (class "Default")
      (node (ref "Q14") (pin "3") (pinfunction "C_3") (pintype "passive"))
      (node (ref "Q22") (pin "2") (pinfunction "E_2") (pintype "passive"))
      (node (ref "R39") (pin "2") (pinfunction "2_2") (pintype "passive"))
    )
    (net (code "43") (name "/NX41E") (class "Default")
      (node (ref "Q14") (pin "2") (pinfunction "E_2") (pintype "passive"))
      (node (ref "R30") (pin "1") (pinfunction "1_1") (pintype "passive"))
    )
    (net (code "44") (name "/NX42C") (class "Default")
      (node (ref "Q23") (pin "2") (pinfunction "E_2") (pintype "passive"))
      (node (ref "Q8") (pin "3") (pinfunction "C_3") (pintype "passive"))
      (node (ref "R40") (pin "2") (pinfunction "2_2") (pintype "passive"))
    )
    (net (code "45") (name "/NX42E") (class "Default")
      (node (ref "Q8") (pin "2") (pinfunction "E_2") (pintype "passive"))
      (node (ref "R20") (pin "1") (pinfunction "1_1") (pintype "passive"))
    )
    (net (code "46") (name "/NXECSC") (class "Default")
      (node (ref "Q10") (pin "3") (pinfunction "C_3") (pintype "passive"))
      (node (ref "Q15") (pin "3") (pinfunction "C_3") (pintype "passive"))
    )
    (net (code "47") (name "/NXECSE") (class "Default")
      (node (ref "Q10") (pin "2") (pinfunction "E_2") (pintype "passive"))
      (node (ref "R26") (pin "1") (pinfunction "1_1") (pintype "passive"))
    )
    (net (code "48") (name "/NXOCSC") (class "Default")
      (node (ref "Q4") (pin "3") (pinfunction "C_3") (pintype "passive"))
      (node (ref "Q9") (pin "3") (pinfunction "C_3") (pintype "passive"))
    )
    (net (code "49") (name "/NXOCSE") (class "Default")
      (node (ref "Q4") (pin "2") (pinfunction "E_2") (pintype "passive"))
      (node (ref "R16") (pin "1") (pinfunction "1_1") (pintype "passive"))
    )
    (net (code "50") (name "/ODD CS VOLTAGE") (class "Default")
      (node (ref "Q4") (pin "1") (pinfunction "B_1") (pintype "passive"))
      (node (ref "Q5") (pin "1") (pinfunction "B_1") (pintype "passive"))
      (node (ref "Q6") (pin "1") (pinfunction "B_1") (pintype "passive"))
      (node (ref "Q7") (pin "1") (pinfunction "B_1") (pintype "passive"))
      (node (ref "Q8") (pin "1") (pinfunction "B_1") (pintype "passive"))
    )
    (net (code "51") (name "/PLATE SEL1") (class "Default")
      (node (ref "Q24") (pin "2") (pinfunction "E_2") (pintype "passive"))
    )
    (net (code "52") (name "/PLATE SEL2") (class "Default")
      (node (ref "Q26") (pin "2") (pinfunction "E_2") (pintype "passive"))
    )
    (net (code "53") (name "/PLATE SEL3") (class "Default")
      (node (ref "Q28") (pin "2") (pinfunction "E_2") (pintype "passive"))
    )
    (net (code "54") (name "/PLATE SEL4") (class "Default")
      (node (ref "Q30") (pin "2") (pinfunction "E_2") (pintype "passive"))
    )
    (net (code "55") (name "B+") (class "Default")
      (node (ref "R16") (pin "2") (pinfunction "2_2") (pintype "passive"))
      (node (ref "R17") (pin "2") (pinfunction "2_2") (pintype "passive"))
      (node (ref "R18") (pin "2") (pinfunction "2_2") (pintype "passive"))
      (node (ref "R19") (pin "2") (pinfunction "2_2") (pintype "passive"))
      (node (ref "R20") (pin "2") (pinfunction "2_2") (pintype "passive"))
      (node (ref "R21") (pin "2") (pinfunction "2_2") (pintype "passive"))
      (node (ref "R26") (pin "2") (pinfunction "2_2") (pintype "passive"))
      (node (ref "R27") (pin "2") (pinfunction "2_2") (pintype "passive"))
      (node (ref "R28") (pin "2") (pinfunction "2_2") (pintype "passive"))
      (node (ref "R29") (pin "2") (pinfunction "2_2") (pintype "passive"))
      (node (ref "R30") (pin "2") (pinfunction "2_2") (pintype "passive"))
      (node (ref "R31") (pin "2") (pinfunction "2_2") (pintype "passive"))
    )
    (net (code "56") (name "GND") (class "Default")
      (node (ref "Q25") (pin "2") (pinfunction "E_2") (pintype "passive"))
      (node (ref "Q27") (pin "2") (pinfunction "E_2") (pintype "passive"))
      (node (ref "Q29") (pin "2") (pinfunction "E_2") (pintype "passive"))
      (node (ref "Q31") (pin "2") (pinfunction "E_2") (pintype "passive"))
      (node (ref "R23") (pin "1") (pinfunction "1_1") (pintype "passive"))
      (node (ref "R24") (pin "1") (pinfunction "1_1") (pintype "passive"))
      (node (ref "R25") (pin "1") (pinfunction "1_1") (pintype "passive"))
      (node (ref "R41") (pin "1") (pinfunction "1_1") (pintype "passive"))
      (node (ref "R42") (pin "1") (pinfunction "1_1") (pintype "passive"))
      (node (ref "R43") (pin "1") (pinfunction "1_1") (pintype "passive"))
      (node (ref "R60") (pin "2") (pinfunction "2_2") (pintype "passive"))
      (node (ref "R61") (pin "2") (pinfunction "2_2") (pintype "passive"))
      (node (ref "R62") (pin "2") (pinfunction "2_2") (pintype "passive"))
      (node (ref "R63") (pin "2") (pinfunction "2_2") (pintype "passive"))
    )
    (net (code "57") (name "Net-(Q9-B)") (class "Default")
      (node (ref "Q9") (pin "1") (pinfunction "B_1") (pintype "passive"))
      (node (ref "R22") (pin "2") (pinfunction "2_2") (pintype "passive"))
    )
    (net (code "58") (name "Net-(Q9-E)") (class "Default")
      (node (ref "Q9") (pin "2") (pinfunction "E_2") (pintype "passive"))
      (node (ref "R25") (pin "2") (pinfunction "2_2") (pintype "passive"))
    )
    (net (code "59") (name "Net-(Q15-B)") (class "Default")
      (node (ref "Q15") (pin "1") (pinfunction "B_1") (pintype "passive"))
      (node (ref "R32") (pin "2") (pinfunction "2_2") (pintype "passive"))
    )
    (net (code "60") (name "Net-(Q15-E)") (class "Default")
      (node (ref "Q15") (pin "2") (pinfunction "E_2") (pintype "passive"))
      (node (ref "R43") (pin "2") (pinfunction "2_2") (pintype "passive"))
    )
    (net (code "61") (name "Net-(Q16-B)") (class "Default")
      (node (ref "Q16") (pin "1") (pinfunction "B_1") (pintype "passive"))
      (node (ref "R33") (pin "1") (pinfunction "1_1") (pintype "passive"))
      (node (ref "R44") (pin "2") (pinfunction "2_2") (pintype "passive"))
    )
    (net (code "62") (name "Net-(Q17-B)") (class "Default")
      (node (ref "Q17") (pin "1") (pinfunction "B_1") (pintype "passive"))
      (node (ref "R34") (pin "1") (pinfunction "1_1") (pintype "passive"))
      (node (ref "R45") (pin "2") (pinfunction "2_2") (pintype "passive"))
    )
    (net (code "63") (name "Net-(Q18-B)") (class "Default")
      (node (ref "Q18") (pin "1") (pinfunction "B_1") (pintype "passive"))
      (node (ref "R35") (pin "1") (pinfunction "1_1") (pintype "passive"))
      (node (ref "R46") (pin "2") (pinfunction "2_2") (pintype "passive"))
    )
    (net (code "64") (name "Net-(Q19-B)") (class "Default")
      (node (ref "Q19") (pin "1") (pinfunction "B_1") (pintype "passive"))
      (node (ref "R36") (pin "1") (pinfunction "1_1") (pintype "passive"))
      (node (ref "R47") (pin "2") (pinfunction "2_2") (pintype "passive"))
    )
    (net (code "65") (name "Net-(Q20-B)") (class "Default")
      (node (ref "Q20") (pin "1") (pinfunction "B_1") (pintype "passive"))
      (node (ref "R37") (pin "1") (pinfunction "1_1") (pintype "passive"))
      (node (ref "R48") (pin "2") (pinfunction "2_2") (pintype "passive"))
    )
    (net (code "66") (name "Net-(Q21-B)") (class "Default")
      (node (ref "Q21") (pin "1") (pinfunction "B_1") (pintype "passive"))
      (node (ref "R38") (pin "1") (pinfunction "1_1") (pintype "passive"))
      (node (ref "R49") (pin "2") (pinfunction "2_2") (pintype "passive"))
    )
    (net (code "67") (name "Net-(Q22-B)") (class "Default")
      (node (ref "Q22") (pin "1") (pinfunction "B_1") (pintype "passive"))
      (node (ref "R39") (pin "1") (pinfunction "1_1") (pintype "passive"))
      (node (ref "R50") (pin "2") (pinfunction "2_2") (pintype "passive"))
    )
    (net (code "68") (name "Net-(Q23-B)") (class "Default")
      (node (ref "Q23") (pin "1") (pinfunction "B_1") (pintype "passive"))
      (node (ref "R40") (pin "1") (pinfunction "1_1") (pintype "passive"))
      (node (ref "R51") (pin "2") (pinfunction "2_2") (pintype "passive"))
    )
    (net (code "69") (name "Net-(Q24-B)") (class "Default")
      (node (ref "Q24") (pin "1") (pinfunction "B_1") (pintype "passive"))
      (node (ref "R52") (pin "1") (pinfunction "1_1") (pintype "passive"))
      (node (ref "R56") (pin "2") (pinfunction "2_2") (pintype "passive"))
    )
    (net (code "70") (name "Net-(Q24-C)") (class "Default")
      (node (ref "Q24") (pin "3") (pinfunction "C_3") (pintype "passive"))
      (node (ref "R44") (pin "1") (pinfunction "1_1") (pintype "passive"))
    )
    (net (code "71") (name "Net-(Q25-B)") (class "Default")
      (node (ref "Q25") (pin "1") (pinfunction "B_1") (pintype "passive"))
      (node (ref "R56") (pin "1") (pinfunction "1_1") (pintype "passive"))
      (node (ref "R60") (pin "1") (pinfunction "1_1") (pintype "passive"))
    )
    (net (code "72") (name "Net-(Q25-C)") (class "Default")
      (node (ref "Q25") (pin "3") (pinfunction "C_3") (pintype "passive"))
      (node (ref "R45") (pin "1") (pinfunction "1_1") (pintype "passive"))
    )
    (net (code "73") (name "Net-(Q26-B)") (class "Default")
      (node (ref "Q26") (pin "1") (pinfunction "B_1") (pintype "passive"))
      (node (ref "R53") (pin "1") (pinfunction "1_1") (pintype "passive"))
      (node (ref "R57") (pin "2") (pinfunction "2_2") (pintype "passive"))
    )
    (net (code "74") (name "Net-(Q26-C)") (class "Default")
      (node (ref "Q26") (pin "3") (pinfunction "C_3") (pintype "passive"))
      (node (ref "R46") (pin "1") (pinfunction "1_1") (pintype "passive"))
    )
    (net (code "75") (name "Net-(Q27-B)") (class "Default")
      (node (ref "Q27") (pin "1") (pinfunction "B_1") (pintype "passive"))
      (node (ref "R57") (pin "1") (pinfunction "1_1") (pintype "passive"))
      (node (ref "R61") (pin "1") (pinfunction "1_1") (pintype "passive"))
    )
    (net (code "76") (name "Net-(Q27-C)") (class "Default")
      (node (ref "Q27") (pin "3") (pinfunction "C_3") (pintype "passive"))
      (node (ref "R47") (pin "1") (pinfunction "1_1") (pintype "passive"))
    )
    (net (code "77") (name "Net-(Q28-B)") (class "Default")
      (node (ref "Q28") (pin "1") (pinfunction "B_1") (pintype "passive"))
      (node (ref "R54") (pin "1") (pinfunction "1_1") (pintype "passive"))
      (node (ref "R58") (pin "2") (pinfunction "2_2") (pintype "passive"))
    )
    (net (code "78") (name "Net-(Q28-C)") (class "Default")
      (node (ref "Q28") (pin "3") (pinfunction "C_3") (pintype "passive"))
      (node (ref "R48") (pin "1") (pinfunction "1_1") (pintype "passive"))
    )
    (net (code "79") (name "Net-(Q29-B)") (class "Default")
      (node (ref "Q29") (pin "1") (pinfunction "B_1") (pintype "passive"))
      (node (ref "R58") (pin "1") (pinfunction "1_1") (pintype "passive"))
      (node (ref "R62") (pin "1") (pinfunction "1_1") (pintype "passive"))
    )
    (net (code "80") (name "Net-(Q29-C)") (class "Default")
      (node (ref "Q29") (pin "3") (pinfunction "C_3") (pintype "passive"))
      (node (ref "R49") (pin "1") (pinfunction "1_1") (pintype "passive"))
    )
    (net (code "81") (name "Net-(Q30-B)") (class "Default")
      (node (ref "Q30") (pin "1") (pinfunction "B_1") (pintype "passive"))
      (node (ref "R55") (pin "1") (pinfunction "1_1") (pintype "passive"))
      (node (ref "R59") (pin "2") (pinfunction "2_2") (pintype "passive"))
    )
    (net (code "82") (name "Net-(Q30-C)") (class "Default")
      (node (ref "Q30") (pin "3") (pinfunction "C_3") (pintype "passive"))
      (node (ref "R50") (pin "1") (pinfunction "1_1") (pintype "passive"))
    )
    (net (code "83") (name "Net-(Q31-B)") (class "Default")
      (node (ref "Q31") (pin "1") (pinfunction "B_1") (pintype "passive"))
      (node (ref "R59") (pin "1") (pinfunction "1_1") (pintype "passive"))
      (node (ref "R63") (pin "1") (pinfunction "1_1") (pintype "passive"))
    )
    (net (code "84") (name "Net-(Q31-C)") (class "Default")
      (node (ref "Q31") (pin "3") (pinfunction "C_3") (pintype "passive"))
      (node (ref "R51") (pin "1") (pinfunction "1_1") (pintype "passive"))
    )
    (net (code "85") (name "Net-(R21-Pad1)") (class "Default")
      (node (ref "R21") (pin "1") (pinfunction "1_1") (pintype "passive"))
      (node (ref "R22") (pin "3") (pinfunction "3_3") (pintype "passive"))
    )
    (net (code "86") (name "Net-(R22-Pad1)") (class "Default")
      (node (ref "R22") (pin "1") (pinfunction "1_1") (pintype "passive"))
      (node (ref "R23") (pin "2") (pinfunction "2_2") (pintype "passive"))
      (node (ref "R24") (pin "2") (pinfunction "2_2") (pintype "passive"))
    )
    (net (code "87") (name "Net-(R31-Pad1)") (class "Default")
      (node (ref "R31") (pin "1") (pinfunction "1_1") (pintype "passive"))
      (node (ref "R32") (pin "3") (pinfunction "3_3") (pintype "passive"))
    )
    (net (code "88") (name "Net-(R32-Pad1)") (class "Default")
      (node (ref "R32") (pin "1") (pinfunction "1_1") (pintype "passive"))
      (node (ref "R41") (pin "2") (pinfunction "2_2") (pintype "passive"))
      (node (ref "R42") (pin "2") (pinfunction "2_2") (pintype "passive"))
    )
    (net (code "89") (name "VCC") (class "Default")
      (node (ref "R52") (pin "2") (pinfunction "2_2") (pintype "passive"))
      (node (ref "R53") (pin "2") (pinfunction "2_2") (pintype "passive"))
      (node (ref "R54") (pin "2") (pinfunction "2_2") (pintype "passive"))
      (node (ref "R55") (pin "2") (pinfunction "2_2") (pintype "passive"))
    )
    (net (code "90") (name "VCOM") (class "Default")
      (node (ref "D5") (pin "4") (pinfunction "S_4") (pintype "passive"))
      (node (ref "D6") (pin "4") (pinfunction "S_4") (pintype "passive"))
      (node (ref "D7") (pin "4") (pinfunction "S_4") (pintype "passive"))
      (node (ref "D8") (pin "4") (pinfunction "S_4") (pintype "passive"))
    )
  )
)
